# DAQ5.net
KiCad netlist of a schematic drawn in EAGLE
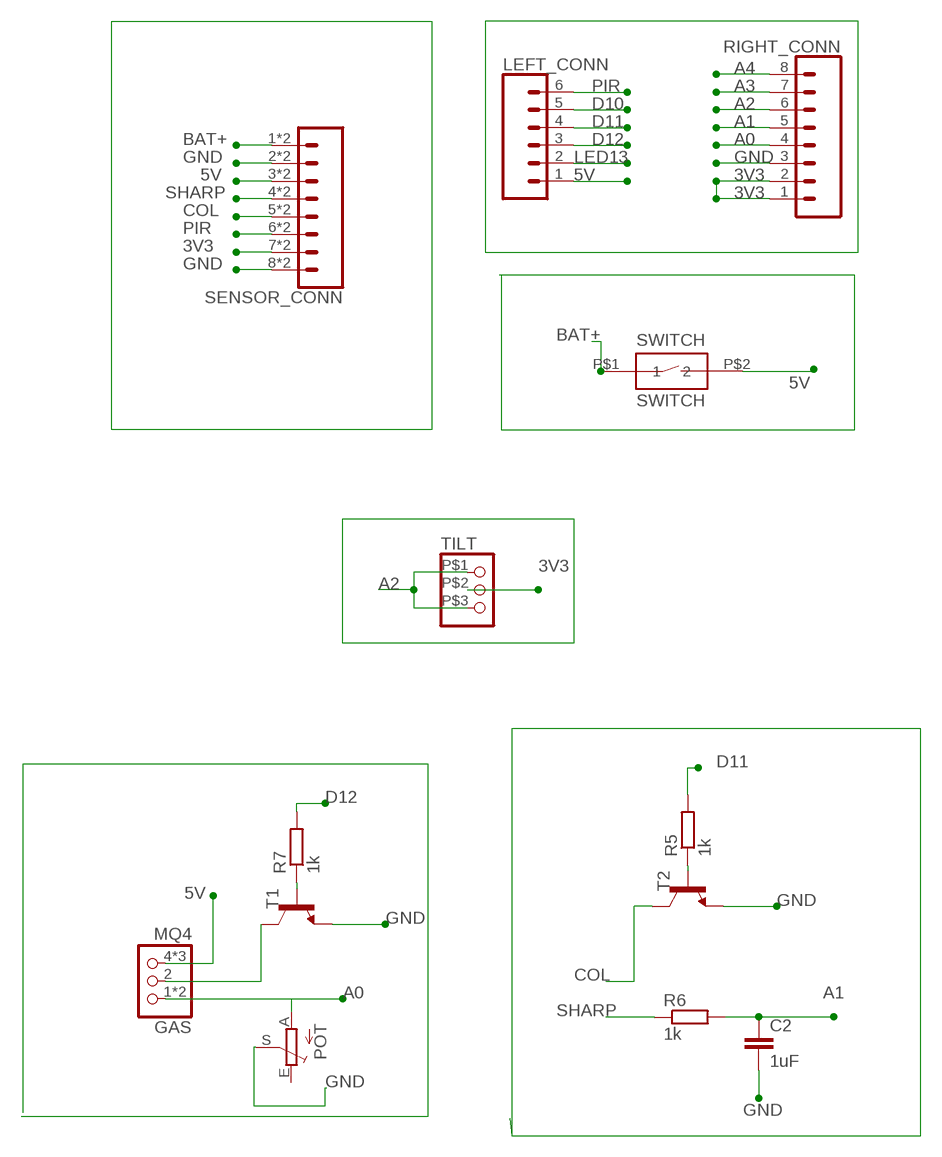
[diagram p0: schematic, sheet 1]

(export (version "E")
  (design (tool "Eeschema 10.0.6"))
  (components
    (comp (ref "C2")
      (value "1uF")
      (footprint "eagle-import:C5B2.5")
      (libsource (lib "eagle-import") (part "C5/2.5"))
    )
    (comp (ref "GAS")
      (value "MQ4")
      (footprint "eagle-import:6PIN_MQ")
      (libsource (lib "eagle-import") (part "MQ4"))
    )
    (comp (ref "LEFT_CONN")
      (value "CONN_06NO_SILK_FEMALE_PTH")
      (footprint "eagle-import:1X06_NO_SILK")
      (libsource (lib "eagle-import") (part "CONN_06NO_SILK_FEMALE_PTH"))
    )
    (comp (ref "POT")
      (value "TRIM_EU-B25P")
      (footprint "eagle-import:B25P")
      (libsource (lib "eagle-import") (part "TRIM_EU-B25P"))
    )
    (comp (ref "R5")
      (value "1k")
      (footprint "eagle-import:R1206")
      (libsource (lib "eagle-import") (part "R-EU_R1206"))
    )
    (comp (ref "R6")
      (value "1k")
      (footprint "eagle-import:R1206")
      (libsource (lib "eagle-import") (part "R-EU_R1206"))
    )
    (comp (ref "R7")
      (value "1k")
      (footprint "eagle-import:R1206")
      (libsource (lib "eagle-import") (part "R-EU_R1206"))
    )
    (comp (ref "RIGHT_CONN")
      (value "CONN_08NO_SILK_FEMALE_PTH")
      (footprint "eagle-import:1X08_NO_SILK")
      (libsource (lib "eagle-import") (part "CONN_08NO_SILK_FEMALE_PTH"))
    )
    (comp (ref "SENSOR_CONN")
      (value "CONN_08")
      (footprint "eagle-import:PHOENIX08")
      (libsource (lib "eagle-import") (part "CONN_08"))
    )
    (comp (ref "SWITCH")
      (value "SWITCH")
      (footprint "eagle-import:SWITCH")
      (libsource (lib "eagle-import") (part "SWITCH"))
    )
    (comp (ref "T1")
      (value "-NPN-TO92-EBC")
      (footprint "eagle-import:TO92-EBC")
      (libsource (lib "eagle-import") (part "-NPN-TO92-EBC"))
    )
    (comp (ref "T2")
      (value "-NPN-TO92-EBC")
      (footprint "eagle-import:TO92-EBC")
      (libsource (lib "eagle-import") (part "-NPN-TO92-EBC"))
    )
    (comp (ref "TILT")
      (value "TILT")
      (footprint "eagle-import:TILT")
      (libsource (lib "eagle-import") (part "TILT"))
    )
  )
  (nets
    (net (code "1") (name "/3V3") (class "Default")
      (node (ref "RIGHT_CONN") (pin "1") (pinfunction "1_1") (pintype "passive"))
      (node (ref "RIGHT_CONN") (pin "2") (pinfunction "2_2") (pintype "passive"))
      (node (ref "SENSOR_CONN") (pin "7") (pinfunction "7_7") (pintype "passive"))
      (node (ref "SENSOR_CONN") (pin "P$7") (pinfunction "7_P$7") (pintype "passive"))
      (node (ref "TILT") (pin "P$2") (pinfunction "2_P$2") (pintype "passive"))
    )
    (net (code "2") (name "/5V") (class "Default")
      (node (ref "GAS") (pin "4") (pinfunction "3_4") (pintype "passive"))
      (node (ref "GAS") (pin "5") (pinfunction "3_5") (pintype "passive"))
      (node (ref "GAS") (pin "6") (pinfunction "3_6") (pintype "passive"))
      (node (ref "LEFT_CONN") (pin "1") (pinfunction "1_1") (pintype "passive"))
      (node (ref "SENSOR_CONN") (pin "3") (pinfunction "3_3") (pintype "passive"))
      (node (ref "SENSOR_CONN") (pin "P$3") (pinfunction "3_P$3") (pintype "passive"))
      (node (ref "SWITCH") (pin "P$2") (pinfunction "2_P$2") (pintype "passive"))
    )
    (net (code "3") (name "/A0") (class "Default")
      (node (ref "GAS") (pin "1") (pinfunction "1_1") (pintype "passive"))
      (node (ref "GAS") (pin "3") (pinfunction "1_3") (pintype "passive"))
      (node (ref "POT") (pin "A") (pinfunction "A_A") (pintype "passive"))
      (node (ref "RIGHT_CONN") (pin "4") (pinfunction "4_4") (pintype "passive"))
    )
    (net (code "4") (name "/A1") (class "Default")
      (node (ref "C2") (pin "1") (pinfunction "1_1") (pintype "passive"))
      (node (ref "R6") (pin "2") (pinfunction "2_2") (pintype "passive"))
      (node (ref "RIGHT_CONN") (pin "5") (pinfunction "5_5") (pintype "passive"))
    )
    (net (code "5") (name "/A2") (class "Default")
      (node (ref "RIGHT_CONN") (pin "6") (pinfunction "6_6") (pintype "passive"))
      (node (ref "TILT") (pin "P$1") (pinfunction "1_P$1") (pintype "passive"))
      (node (ref "TILT") (pin "P$3") (pinfunction "3_P$3") (pintype "passive"))
    )
    (net (code "6") (name "/A3") (class "Default")
      (node (ref "RIGHT_CONN") (pin "7") (pinfunction "7_7") (pintype "passive"))
    )
    (net (code "7") (name "/A4") (class "Default")
      (node (ref "RIGHT_CONN") (pin "8") (pinfunction "8_8") (pintype "passive"))
    )
    (net (code "8") (name "/BAT+") (class "Default")
      (node (ref "SENSOR_CONN") (pin "1") (pinfunction "1_1") (pintype "passive"))
      (node (ref "SENSOR_CONN") (pin "P$1") (pinfunction "1_P$1") (pintype "passive"))
      (node (ref "SWITCH") (pin "P$1") (pinfunction "1_P$1") (pintype "passive"))
    )
    (net (code "9") (name "/COL") (class "Default")
      (node (ref "SENSOR_CONN") (pin "5") (pinfunction "5_5") (pintype "passive"))
      (node (ref "SENSOR_CONN") (pin "P$5") (pinfunction "5_P$5") (pintype "passive"))
      (node (ref "T2") (pin "C") (pinfunction "C_C") (pintype "passive"))
    )
    (net (code "10") (name "/D10") (class "Default")
      (node (ref "LEFT_CONN") (pin "5") (pinfunction "5_5") (pintype "passive"))
    )
    (net (code "11") (name "/D11") (class "Default")
      (node (ref "LEFT_CONN") (pin "4") (pinfunction "4_4") (pintype "passive"))
      (node (ref "R5") (pin "2") (pinfunction "2_2") (pintype "passive"))
    )
    (net (code "12") (name "/D12") (class "Default")
      (node (ref "LEFT_CONN") (pin "3") (pinfunction "3_3") (pintype "passive"))
      (node (ref "R7") (pin "2") (pinfunction "2_2") (pintype "passive"))
    )
    (net (code "13") (name "/GND") (class "Default")
      (node (ref "C2") (pin "2") (pinfunction "2_2") (pintype "passive"))
      (node (ref "POT") (pin "S") (pinfunction "S_S") (pintype "passive"))
      (node (ref "RIGHT_CONN") (pin "3") (pinfunction "3_3") (pintype "passive"))
      (node (ref "SENSOR_CONN") (pin "2") (pinfunction "2_2") (pintype "passive"))
      (node (ref "SENSOR_CONN") (pin "8") (pinfunction "8_8") (pintype "passive"))
      (node (ref "SENSOR_CONN") (pin "P$2") (pinfunction "2_P$2") (pintype "passive"))
      (node (ref "SENSOR_CONN") (pin "P$8") (pinfunction "8_P$8") (pintype "passive"))
      (node (ref "T1") (pin "E") (pinfunction "E_E") (pintype "passive"))
      (node (ref "T2") (pin "E") (pinfunction "E_E") (pintype "passive"))
    )
    (net (code "14") (name "/LED13") (class "Default")
      (node (ref "LEFT_CONN") (pin "2") (pinfunction "2_2") (pintype "passive"))
    )
    (net (code "15") (name "/PIR") (class "Default")
      (node (ref "LEFT_CONN") (pin "6") (pinfunction "6_6") (pintype "passive"))
      (node (ref "SENSOR_CONN") (pin "6") (pinfunction "6_6") (pintype "passive"))
      (node (ref "SENSOR_CONN") (pin "P$6") (pinfunction "6_P$6") (pintype "passive"))
    )
    (net (code "16") (name "/SHARP") (class "Default")
      (node (ref "R6") (pin "1") (pinfunction "1_1") (pintype "passive"))
      (node (ref "SENSOR_CONN") (pin "4") (pinfunction "4_4") (pintype "passive"))
      (node (ref "SENSOR_CONN") (pin "P$4") (pinfunction "4_P$4") (pintype "passive"))
    )
    (net (code "17") (name "Net-(GAS-Pad2)") (class "Default")
      (node (ref "GAS") (pin "2") (pinfunction "2_2") (pintype "passive"))
      (node (ref "T1") (pin "C") (pinfunction "C_C") (pintype "passive"))
    )
    (net (code "18") (name "Net-(R5-Pad1)") (class "Default")
      (node (ref "R5") (pin "1") (pinfunction "1_1") (pintype "passive"))
      (node (ref "T2") (pin "B") (pinfunction "B_B") (pintype "passive"))
    )
    (net (code "19") (name "Net-(R7-Pad1)") (class "Default")
      (node (ref "R7") (pin "1") (pinfunction "1_1") (pintype "passive"))
      (node (ref "T1") (pin "B") (pinfunction "B_B") (pintype "passive"))
    )
    (net (code "20") (name "unconnected-(POT-PadE)") (class "Default")
      (node (ref "POT") (pin "E") (pinfunction "E_E") (pintype "passive"))
    )
  )
)
